# ab-berry-rev2.net
KiCad netlist of a schematic drawn in EAGLE
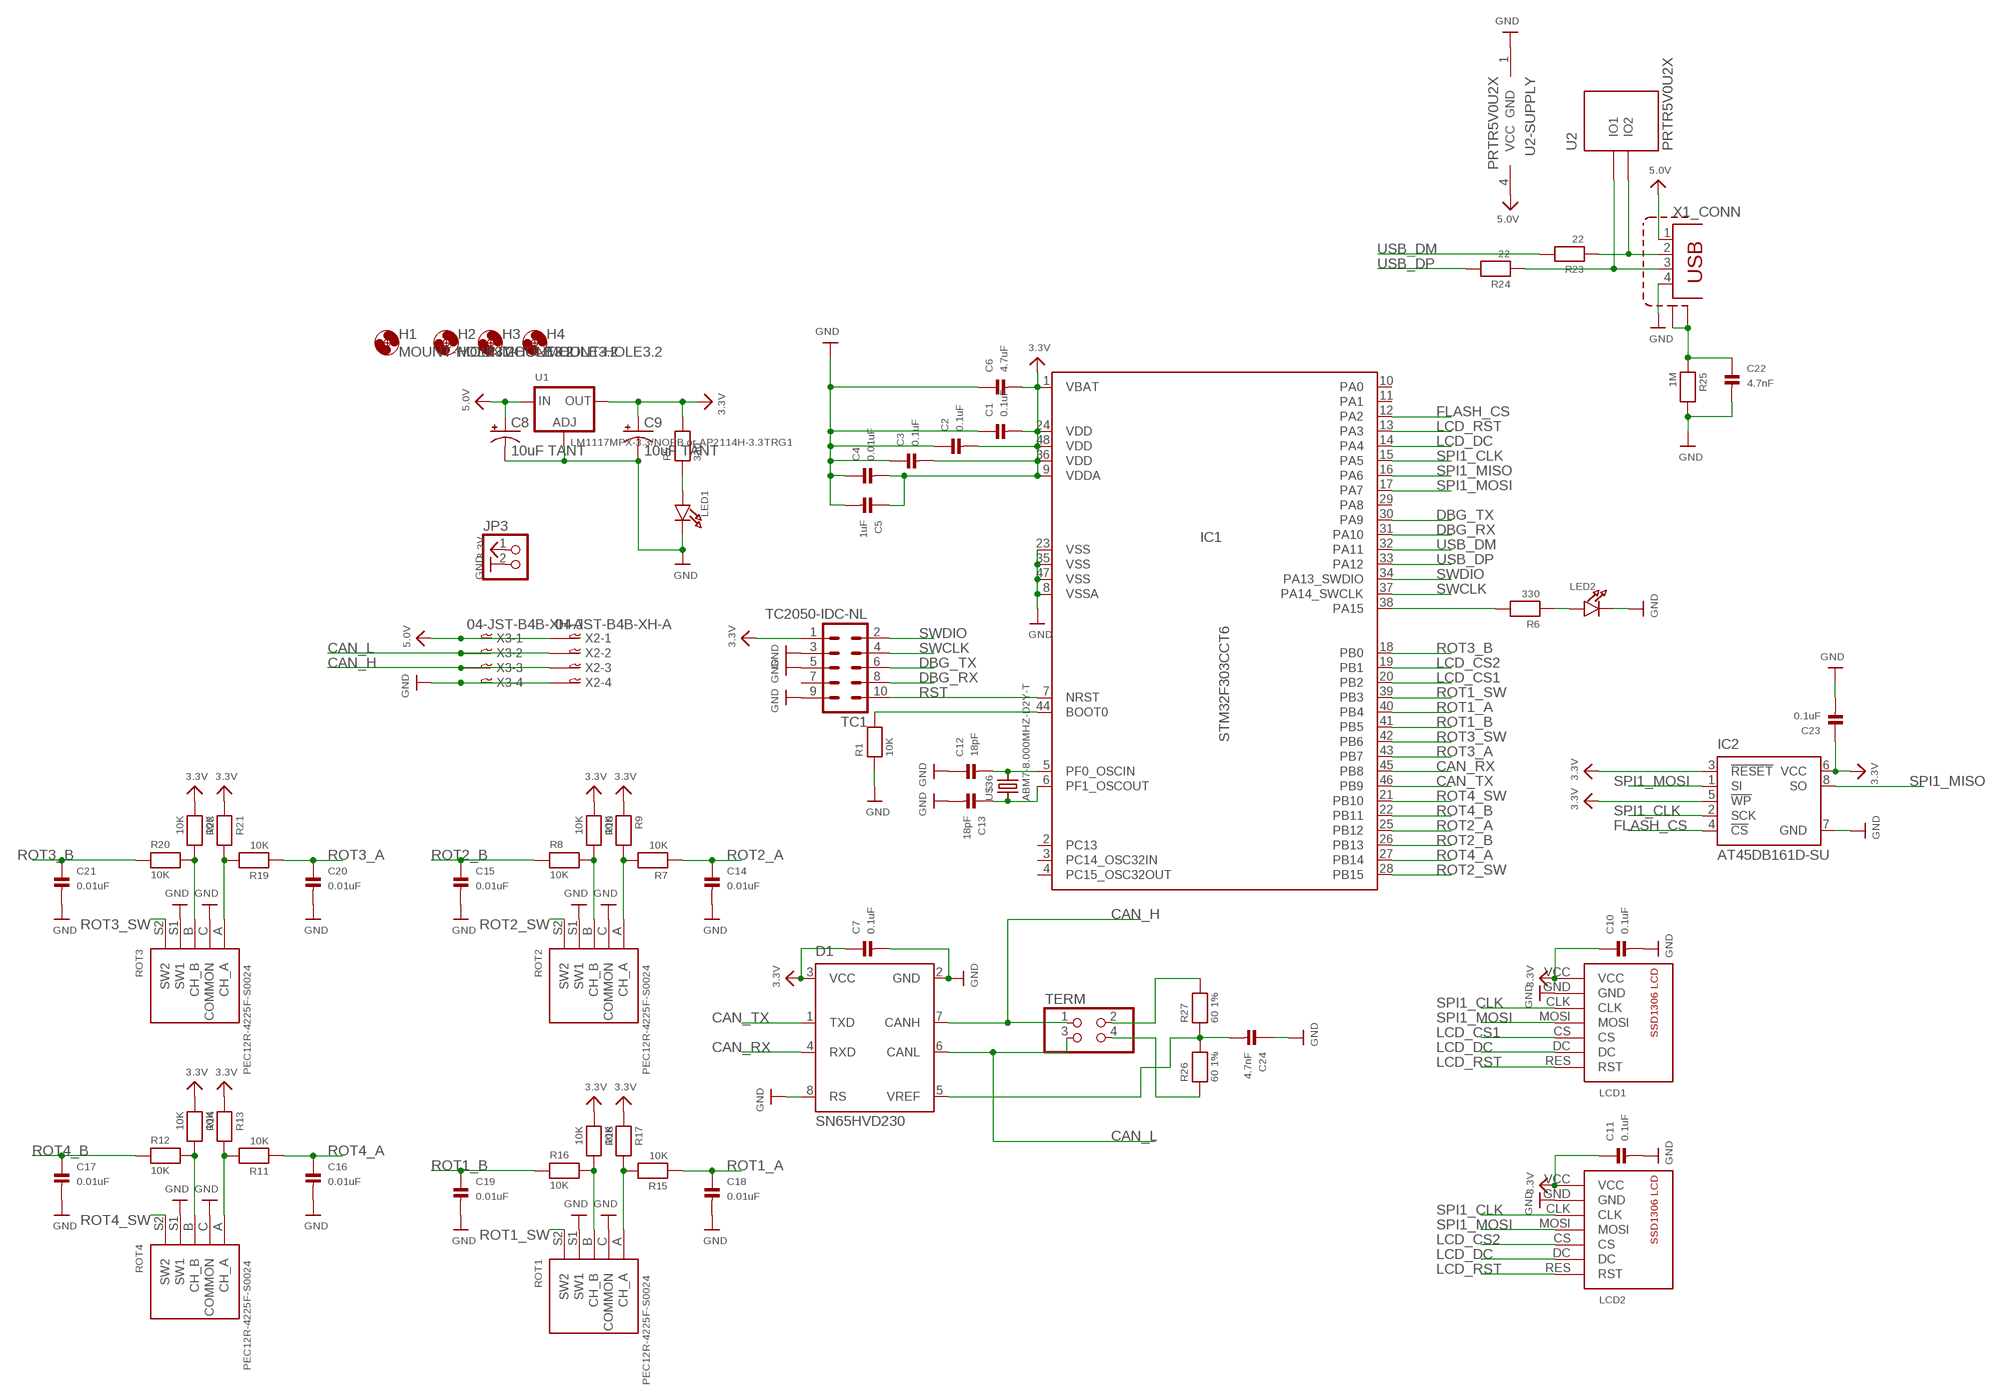
[diagram p0: schematic, sheet 1]

(export (version "E")
  (design (tool "Eeschema 10.0.6"))
  (components
    (comp (ref "C1")
      (value "0.1uF")
      (footprint "eagle-import:0603")
      (libsource (lib "eagle-import") (part "CAP_CERAMIC0603"))
    )
    (comp (ref "C2")
      (value "0.1uF")
      (footprint "eagle-import:0603")
      (libsource (lib "eagle-import") (part "CAP_CERAMIC0603"))
    )
    (comp (ref "C3")
      (value "0.1uF")
      (footprint "eagle-import:0603")
      (libsource (lib "eagle-import") (part "CAP_CERAMIC0603"))
    )
    (comp (ref "C4")
      (value "0.01uF")
      (footprint "eagle-import:0603")
      (libsource (lib "eagle-import") (part "CAP_CERAMIC0603"))
    )
    (comp (ref "C5")
      (value "1uF")
      (footprint "eagle-import:0603")
      (libsource (lib "eagle-import") (part "CAP_CERAMIC0603"))
    )
    (comp (ref "C6")
      (value "4.7uF")
      (footprint "eagle-import:0603")
      (libsource (lib "eagle-import") (part "CAP_CERAMIC0603"))
    )
    (comp (ref "C7")
      (value "0.1uF")
      (footprint "eagle-import:0603")
      (libsource (lib "eagle-import") (part "CAP_CERAMIC0603"))
    )
    (comp (ref "C8")
      (value "10uF TANT")
      (footprint "eagle-import:0603-POL")
      (libsource (lib "eagle-import") (part "10UF-6.3V-20%(0603)(TANT){dblquote}"))
    )
    (comp (ref "C9")
      (value "10uF TANT")
      (footprint "eagle-import:0603-POL")
      (libsource (lib "eagle-import") (part "10UF-6.3V-20%(0603)(TANT){dblquote}"))
    )
    (comp (ref "C10")
      (value "0.1uF")
      (footprint "eagle-import:0603")
      (libsource (lib "eagle-import") (part "CAP_CERAMIC0603"))
    )
    (comp (ref "C11")
      (value "0.1uF")
      (footprint "eagle-import:0603")
      (libsource (lib "eagle-import") (part "CAP_CERAMIC0603"))
    )
    (comp (ref "C12")
      (value "18pF")
      (footprint "eagle-import:0603")
      (libsource (lib "eagle-import") (part "CAP_CERAMIC0603"))
    )
    (comp (ref "C13")
      (value "18pF")
      (footprint "eagle-import:0603")
      (libsource (lib "eagle-import") (part "CAP_CERAMIC0603"))
    )
    (comp (ref "C14")
      (value "0.01uF")
      (footprint "eagle-import:0603")
      (libsource (lib "eagle-import") (part "CAP_CERAMIC0603"))
    )
    (comp (ref "C15")
      (value "0.01uF")
      (footprint "eagle-import:0603")
      (libsource (lib "eagle-import") (part "CAP_CERAMIC0603"))
    )
    (comp (ref "C16")
      (value "0.01uF")
      (footprint "eagle-import:0603")
      (libsource (lib "eagle-import") (part "CAP_CERAMIC0603"))
    )
    (comp (ref "C17")
      (value "0.01uF")
      (footprint "eagle-import:0603")
      (libsource (lib "eagle-import") (part "CAP_CERAMIC0603"))
    )
    (comp (ref "C18")
      (value "0.01uF")
      (footprint "eagle-import:0603")
      (libsource (lib "eagle-import") (part "CAP_CERAMIC0603"))
    )
    (comp (ref "C19")
      (value "0.01uF")
      (footprint "eagle-import:0603")
      (libsource (lib "eagle-import") (part "CAP_CERAMIC0603"))
    )
    (comp (ref "C20")
      (value "0.01uF")
      (footprint "eagle-import:0603")
      (libsource (lib "eagle-import") (part "CAP_CERAMIC0603"))
    )
    (comp (ref "C21")
      (value "0.01uF")
      (footprint "eagle-import:0603")
      (libsource (lib "eagle-import") (part "CAP_CERAMIC0603"))
    )
    (comp (ref "C22")
      (value "4.7nF")
      (footprint "eagle-import:0603")
      (libsource (lib "eagle-import") (part "CAP_CERAMIC0603"))
    )
    (comp (ref "C23")
      (value "0.1uF")
      (footprint "eagle-import:0603")
      (libsource (lib "eagle-import") (part "CAP_CERAMIC0603"))
    )
    (comp (ref "C24")
      (value "4.7nF")
      (footprint "eagle-import:0603")
      (libsource (lib "eagle-import") (part "CAP_CERAMIC0603"))
    )
    (comp (ref "D1")
      (value "SN65HVD230")
      (footprint "eagle-import:SO8")
      (libsource (lib "eagle-import") (part "SN65HVD230"))
    )
    (comp (ref "H1")
      (value "MOUNT-HOLE3.2")
      (footprint "eagle-import:3,2")
      (libsource (lib "eagle-import") (part "MOUNT-HOLE3.2"))
    )
    (comp (ref "H2")
      (value "MOUNT-HOLE3.2")
      (footprint "eagle-import:3,2")
      (libsource (lib "eagle-import") (part "MOUNT-HOLE3.2"))
    )
    (comp (ref "H3")
      (value "MOUNT-HOLE3.2")
      (footprint "eagle-import:3,2")
      (libsource (lib "eagle-import") (part "MOUNT-HOLE3.2"))
    )
    (comp (ref "H4")
      (value "MOUNT-HOLE3.2")
      (footprint "eagle-import:3,2")
      (libsource (lib "eagle-import") (part "MOUNT-HOLE3.2"))
    )
    (comp (ref "IC1")
      (value "STM32F303CCT6")
      (footprint "eagle-import:TQFP48")
      (libsource (lib "eagle-import") (part "STM32F302_F303_B_C_LQFP48"))
    )
    (comp (ref "IC2")
      (value "AT45DB161D-SU")
      (footprint "eagle-import:8S2")
      (fields (field (name "MF") "ATMEL"))
      (libsource (lib "eagle-import") (part "AT45DB161D-SU"))
    )
    (comp (ref "JP3")
      (value "PINHD-1X2")
      (footprint "eagle-import:1X02")
      (libsource (lib "eagle-import") (part "PINHD-1X2"))
    )
    (comp (ref "LCD1")
      (value "SSD1306-7PINWITHOUT-HOLES")
      (footprint "eagle-import:SSD1306-7PIN-NO-HOLES")
      (libsource (lib "eagle-import") (part "SSD1306-7PINWITHOUT-HOLES"))
    )
    (comp (ref "LCD2")
      (value "SSD1306-7PINWITHOUT-HOLES")
      (footprint "eagle-import:SSD1306-7PIN-NO-HOLES")
      (libsource (lib "eagle-import") (part "SSD1306-7PINWITHOUT-HOLES"))
    )
    (comp (ref "LED1")
      (value "LED0603")
      (footprint "eagle-import:CHIPLED_0603")
      (libsource (lib "eagle-import") (part "LED0603"))
    )
    (comp (ref "LED2")
      (value "LED0603")
      (footprint "eagle-import:CHIPLED_0603")
      (libsource (lib "eagle-import") (part "LED0603"))
    )
    (comp (ref "R1")
      (value "10K")
      (footprint "eagle-import:0603")
      (libsource (lib "eagle-import") (part "RESISTOR0603"))
    )
    (comp (ref "R5")
      (value "330")
      (footprint "eagle-import:0603")
      (libsource (lib "eagle-import") (part "RESISTOR0603"))
    )
    (comp (ref "R6")
      (value "330")
      (footprint "eagle-import:0603")
      (libsource (lib "eagle-import") (part "RESISTOR0603"))
    )
    (comp (ref "R7")
      (value "10K")
      (footprint "eagle-import:0603")
      (libsource (lib "eagle-import") (part "RESISTOR0603"))
    )
    (comp (ref "R8")
      (value "10K")
      (footprint "eagle-import:0603")
      (libsource (lib "eagle-import") (part "RESISTOR0603"))
    )
    (comp (ref "R9")
      (value "10K")
      (footprint "eagle-import:0603")
      (libsource (lib "eagle-import") (part "RESISTOR0603"))
    )
    (comp (ref "R10")
      (value "10K")
      (footprint "eagle-import:0603")
      (libsource (lib "eagle-import") (part "RESISTOR0603"))
    )
    (comp (ref "R11")
      (value "10K")
      (footprint "eagle-import:0603")
      (libsource (lib "eagle-import") (part "RESISTOR0603"))
    )
    (comp (ref "R12")
      (value "10K")
      (footprint "eagle-import:0603")
      (libsource (lib "eagle-import") (part "RESISTOR0603"))
    )
    (comp (ref "R13")
      (value "10K")
      (footprint "eagle-import:0603")
      (libsource (lib "eagle-import") (part "RESISTOR0603"))
    )
    (comp (ref "R14")
      (value "10K")
      (footprint "eagle-import:0603")
      (libsource (lib "eagle-import") (part "RESISTOR0603"))
    )
    (comp (ref "R15")
      (value "10K")
      (footprint "eagle-import:0603")
      (libsource (lib "eagle-import") (part "RESISTOR0603"))
    )
    (comp (ref "R16")
      (value "10K")
      (footprint "eagle-import:0603")
      (libsource (lib "eagle-import") (part "RESISTOR0603"))
    )
    (comp (ref "R17")
      (value "10K")
      (footprint "eagle-import:0603")
      (libsource (lib "eagle-import") (part "RESISTOR0603"))
    )
    (comp (ref "R18")
      (value "10K")
      (footprint "eagle-import:0603")
      (libsource (lib "eagle-import") (part "RESISTOR0603"))
    )
    (comp (ref "R19")
      (value "10K")
      (footprint "eagle-import:0603")
      (libsource (lib "eagle-import") (part "RESISTOR0603"))
    )
    (comp (ref "R20")
      (value "10K")
      (footprint "eagle-import:0603")
      (libsource (lib "eagle-import") (part "RESISTOR0603"))
    )
    (comp (ref "R21")
      (value "10K")
      (footprint "eagle-import:0603")
      (libsource (lib "eagle-import") (part "RESISTOR0603"))
    )
    (comp (ref "R22")
      (value "10K")
      (footprint "eagle-import:0603")
      (libsource (lib "eagle-import") (part "RESISTOR0603"))
    )
    (comp (ref "R23")
      (value "22")
      (footprint "eagle-import:0603")
      (libsource (lib "eagle-import") (part "RESISTOR0603"))
    )
    (comp (ref "R24")
      (value "22")
      (footprint "eagle-import:0603")
      (libsource (lib "eagle-import") (part "RESISTOR0603"))
    )
    (comp (ref "R25")
      (value "1M")
      (footprint "eagle-import:0603")
      (libsource (lib "eagle-import") (part "RESISTOR0603"))
    )
    (comp (ref "R26")
      (value "60 1%")
      (footprint "eagle-import:0603")
      (libsource (lib "eagle-import") (part "RESISTOR0603"))
    )
    (comp (ref "R27")
      (value "60 1%")
      (footprint "eagle-import:0603")
      (libsource (lib "eagle-import") (part "RESISTOR0603"))
    )
    (comp (ref "ROT1")
      (value "PEC12R-4225F-S0024")
      (footprint "eagle-import:PEC111-4XXXK-SXXXX")
      (libsource (lib "eagle-import") (part "PEC11-4215K-S0024"))
    )
    (comp (ref "ROT2")
      (value "PEC12R-4225F-S0024")
      (footprint "eagle-import:PEC111-4XXXK-SXXXX")
      (libsource (lib "eagle-import") (part "PEC11-4215K-S0024"))
    )
    (comp (ref "ROT3")
      (value "PEC12R-4225F-S0024")
      (footprint "eagle-import:PEC111-4XXXK-SXXXX")
      (libsource (lib "eagle-import") (part "PEC11-4215K-S0024"))
    )
    (comp (ref "ROT4")
      (value "PEC12R-4225F-S0024")
      (footprint "eagle-import:PEC111-4XXXK-SXXXX")
      (libsource (lib "eagle-import") (part "PEC11-4215K-S0024"))
    )
    (comp (ref "TC1")
      (value "TC2050-IDC-NL")
      (footprint "eagle-import:TC2050-IDC-NL")
      (libsource (lib "eagle-import") (part "TC2050-IDC-NL"))
    )
    (comp (ref "TERM")
      (value "PINHD-2X2")
      (footprint "eagle-import:2X02")
      (libsource (lib "eagle-import") (part "PINHD-2X2"))
    )
    (comp (ref "U$36")
      (value "ABM7-8.000MHZ-D2Y-T")
      (footprint "eagle-import:ABM7-8.000MHZ-D2Y-T")
      (libsource (lib "eagle-import") (part "ABM7-8.000MHZ-D2Y-T"))
    )
    (comp (ref "U1")
      (value "LM1117MPX-3.3/NOPB or AP2114H-3.3TRG1")
      (footprint "eagle-import:SOT223-R")
      (libsource (lib "eagle-import") (part "LM1117SOT223-REFLOW"))
    )
    (comp (ref "U2")
      (value "PRTR5V0U2X")
      (footprint "eagle-import:SOT-143B")
      (fields
        (field (name "MANUFACTURER") "NXP Semiconductors")
        (field (name "PART_NUMBER") "PRTR5V0U2X,215")
      )
      (libsource (lib "eagle-import") (part "PRTR5V0U2X?"))
    )
    (comp (ref "X1")
      (value "TE-292304-1")
      (footprint "eagle-import:TE-292304-1")
      (libsource (lib "eagle-import") (part "TE-292304-1"))
    )
    (comp (ref "X2")
      (value "04-JST-B4B-XH-A")
      (footprint "eagle-import:B4B-XH")
      (libsource (lib "eagle-import") (part "04-JST-B4B-XH-A"))
    )
    (comp (ref "X3")
      (value "04-JST-B4B-XH-A")
      (footprint "eagle-import:B4B-XH")
      (libsource (lib "eagle-import") (part "04-JST-B4B-XH-A"))
    )
  )
  (nets
    (net (code "1") (name "/CAN_H") (class "Default")
      (node (ref "D1") (pin "7") (pinfunction "CANH_7") (pintype "bidirectional"))
      (node (ref "TERM") (pin "1") (pinfunction "1_1") (pintype "passive"))
      (node (ref "X2") (pin "P$3") (pinfunction "1_P$3") (pintype "passive"))
      (node (ref "X3") (pin "P$3") (pinfunction "1_P$3") (pintype "passive"))
    )
    (net (code "2") (name "/CAN_L") (class "Default")
      (node (ref "D1") (pin "6") (pinfunction "CANL_6") (pintype "bidirectional"))
      (node (ref "TERM") (pin "3") (pinfunction "3_3") (pintype "passive"))
      (node (ref "X2") (pin "P$2") (pinfunction "1_P$2") (pintype "passive"))
      (node (ref "X3") (pin "P$2") (pinfunction "1_P$2") (pintype "passive"))
    )
    (net (code "3") (name "/CAN_RX") (class "Default")
      (node (ref "D1") (pin "4") (pinfunction "RXD_4") (pintype "output"))
      (node (ref "IC1") (pin "45") (pinfunction "PB8_45") (pintype "bidirectional"))
    )
    (net (code "4") (name "/CAN_TX") (class "Default")
      (node (ref "D1") (pin "1") (pinfunction "TXD_1") (pintype "input"))
      (node (ref "IC1") (pin "46") (pinfunction "PB9_46") (pintype "bidirectional"))
    )
    (net (code "5") (name "/DBG_RX") (class "Default")
      (node (ref "IC1") (pin "31") (pinfunction "PA10_31") (pintype "bidirectional"))
      (node (ref "TC1") (pin "8") (pinfunction "8_8") (pintype "passive"))
    )
    (net (code "6") (name "/DBG_TX") (class "Default")
      (node (ref "IC1") (pin "30") (pinfunction "PA9_30") (pintype "bidirectional"))
      (node (ref "TC1") (pin "6") (pinfunction "6_6") (pintype "passive"))
    )
    (net (code "7") (name "/FLASH_CS") (class "Default")
      (node (ref "IC1") (pin "12") (pinfunction "PA2_12") (pintype "bidirectional"))
      (node (ref "IC2") (pin "4") (pinfunction "~{CS}_4") (pintype "input"))
    )
    (net (code "8") (name "/LCD_CS1") (class "Default")
      (node (ref "IC1") (pin "20") (pinfunction "PB2_20") (pintype "bidirectional"))
      (node (ref "LCD1") (pin "CS") (pinfunction "CS_CS") (pintype "bidirectional"))
    )
    (net (code "9") (name "/LCD_CS2") (class "Default")
      (node (ref "IC1") (pin "19") (pinfunction "PB1_19") (pintype "bidirectional"))
      (node (ref "LCD2") (pin "CS") (pinfunction "CS_CS") (pintype "bidirectional"))
    )
    (net (code "10") (name "/LCD_DC") (class "Default")
      (node (ref "IC1") (pin "14") (pinfunction "PA4_14") (pintype "bidirectional"))
      (node (ref "LCD1") (pin "DC") (pinfunction "DC_DC") (pintype "bidirectional"))
      (node (ref "LCD2") (pin "DC") (pinfunction "DC_DC") (pintype "bidirectional"))
    )
    (net (code "11") (name "/LCD_RST") (class "Default")
      (node (ref "IC1") (pin "13") (pinfunction "PA3_13") (pintype "bidirectional"))
      (node (ref "LCD1") (pin "RES") (pinfunction "RST_RES") (pintype "bidirectional"))
      (node (ref "LCD2") (pin "RES") (pinfunction "RST_RES") (pintype "bidirectional"))
    )
    (net (code "12") (name "/ROT1_A") (class "Default")
      (node (ref "C18") (pin "1") (pinfunction "P$1_1") (pintype "passive"))
      (node (ref "IC1") (pin "40") (pinfunction "PB4_40") (pintype "input"))
      (node (ref "R15") (pin "1") (pinfunction "1_1") (pintype "passive"))
    )
    (net (code "13") (name "/ROT1_B") (class "Default")
      (node (ref "C19") (pin "1") (pinfunction "P$1_1") (pintype "passive"))
      (node (ref "IC1") (pin "41") (pinfunction "PB5_41") (pintype "bidirectional"))
      (node (ref "R16") (pin "1") (pinfunction "1_1") (pintype "passive"))
    )
    (net (code "14") (name "/ROT1_SW") (class "Default")
      (node (ref "IC1") (pin "39") (pinfunction "PB3_39") (pintype "output"))
      (node (ref "ROT1") (pin "S2") (pinfunction "SW2_S2") (pintype "bidirectional"))
    )
    (net (code "15") (name "/ROT2_A") (class "Default")
      (node (ref "C14") (pin "1") (pinfunction "P$1_1") (pintype "passive"))
      (node (ref "IC1") (pin "25") (pinfunction "PB12_25") (pintype "bidirectional"))
      (node (ref "R7") (pin "1") (pinfunction "1_1") (pintype "passive"))
    )
    (net (code "16") (name "/ROT2_B") (class "Default")
      (node (ref "C15") (pin "1") (pinfunction "P$1_1") (pintype "passive"))
      (node (ref "IC1") (pin "26") (pinfunction "PB13_26") (pintype "bidirectional"))
      (node (ref "R8") (pin "1") (pinfunction "1_1") (pintype "passive"))
    )
    (net (code "17") (name "/ROT2_SW") (class "Default")
      (node (ref "IC1") (pin "28") (pinfunction "PB15_28") (pintype "bidirectional"))
      (node (ref "ROT2") (pin "S2") (pinfunction "SW2_S2") (pintype "bidirectional"))
    )
    (net (code "18") (name "/ROT3_A") (class "Default")
      (node (ref "C20") (pin "1") (pinfunction "P$1_1") (pintype "passive"))
      (node (ref "IC1") (pin "43") (pinfunction "PB7_43") (pintype "bidirectional"))
      (node (ref "R19") (pin "1") (pinfunction "1_1") (pintype "passive"))
    )
    (net (code "19") (name "/ROT3_B") (class "Default")
      (node (ref "C21") (pin "1") (pinfunction "P$1_1") (pintype "passive"))
      (node (ref "IC1") (pin "18") (pinfunction "PB0_18") (pintype "bidirectional"))
      (node (ref "R20") (pin "1") (pinfunction "1_1") (pintype "passive"))
    )
    (net (code "20") (name "/ROT3_SW") (class "Default")
      (node (ref "IC1") (pin "42") (pinfunction "PB6_42") (pintype "bidirectional"))
      (node (ref "ROT3") (pin "S2") (pinfunction "SW2_S2") (pintype "bidirectional"))
    )
    (net (code "21") (name "/ROT4_A") (class "Default")
      (node (ref "C16") (pin "1") (pinfunction "P$1_1") (pintype "passive"))
      (node (ref "IC1") (pin "27") (pinfunction "PB14_27") (pintype "bidirectional"))
      (node (ref "R11") (pin "1") (pinfunction "1_1") (pintype "passive"))
    )
    (net (code "22") (name "/ROT4_B") (class "Default")
      (node (ref "C17") (pin "1") (pinfunction "P$1_1") (pintype "passive"))
      (node (ref "IC1") (pin "22") (pinfunction "PB11_22") (pintype "bidirectional"))
      (node (ref "R12") (pin "1") (pinfunction "1_1") (pintype "passive"))
    )
    (net (code "23") (name "/ROT4_SW") (class "Default")
      (node (ref "IC1") (pin "21") (pinfunction "PB10_21") (pintype "bidirectional"))
      (node (ref "ROT4") (pin "S2") (pinfunction "SW2_S2") (pintype "bidirectional"))
    )
    (net (code "24") (name "/RST") (class "Default")
      (node (ref "IC1") (pin "7") (pinfunction "NRST_7") (pintype "input"))
      (node (ref "TC1") (pin "10") (pinfunction "10_10") (pintype "passive"))
    )
    (net (code "25") (name "/SPI1_CLK") (class "Default")
      (node (ref "IC1") (pin "15") (pinfunction "PA5_15") (pintype "bidirectional"))
      (node (ref "IC2") (pin "2") (pinfunction "SCK_2") (pintype "input"))
      (node (ref "LCD1") (pin "CLK") (pinfunction "CLK_CLK") (pintype "bidirectional"))
      (node (ref "LCD2") (pin "CLK") (pinfunction "CLK_CLK") (pintype "bidirectional"))
    )
    (net (code "26") (name "/SPI1_MISO") (class "Default")
      (node (ref "IC1") (pin "16") (pinfunction "PA6_16") (pintype "bidirectional"))
      (node (ref "IC2") (pin "8") (pinfunction "SO_8") (pintype "output"))
    )
    (net (code "27") (name "/SPI1_MOSI") (class "Default")
      (node (ref "IC1") (pin "17") (pinfunction "PA7_17") (pintype "bidirectional"))
      (node (ref "IC2") (pin "1") (pinfunction "SI_1") (pintype "input"))
      (node (ref "LCD1") (pin "MOSI") (pinfunction "MOSI_MOSI") (pintype "bidirectional"))
      (node (ref "LCD2") (pin "MOSI") (pinfunction "MOSI_MOSI") (pintype "bidirectional"))
    )
    (net (code "28") (name "/SWCLK") (class "Default")
      (node (ref "IC1") (pin "37") (pinfunction "PA14_SWCLK_37") (pintype "input"))
      (node (ref "TC1") (pin "4") (pinfunction "4_4") (pintype "passive"))
    )
    (net (code "29") (name "/SWDIO") (class "Default")
      (node (ref "IC1") (pin "34") (pinfunction "PA13_SWDIO_34") (pintype "input"))
      (node (ref "TC1") (pin "2") (pinfunction "2_2") (pintype "passive"))
    )
    (net (code "30") (name "/USB_DM") (class "Default")
      (node (ref "IC1") (pin "32") (pinfunction "PA11_32") (pintype "bidirectional"))
      (node (ref "R23") (pin "2") (pinfunction "2_2") (pintype "passive"))
    )
    (net (code "31") (name "/USB_DP") (class "Default")
      (node (ref "IC1") (pin "33") (pinfunction "PA12_33") (pintype "bidirectional"))
      (node (ref "R24") (pin "2") (pinfunction "2_2") (pintype "passive"))
    )
    (net (code "32") (name "3.3V") (class "Default")
      (node (ref "C1") (pin "2") (pinfunction "P$2_2") (pintype "passive"))
      (node (ref "C10") (pin "1") (pinfunction "P$1_1") (pintype "passive"))
      (node (ref "C11") (pin "1") (pinfunction "P$1_1") (pintype "passive"))
      (node (ref "C2") (pin "2") (pinfunction "P$2_2") (pintype "passive"))
      (node (ref "C23") (pin "1") (pinfunction "P$1_1") (pintype "passive"))
      (node (ref "C3") (pin "2") (pinfunction "P$2_2") (pintype "passive"))
      (node (ref "C4") (pin "2") (pinfunction "P$2_2") (pintype "passive"))
      (node (ref "C5") (pin "1") (pinfunction "P$1_1") (pintype "passive"))
      (node (ref "C6") (pin "2") (pinfunction "P$2_2") (pintype "passive"))
      (node (ref "C7") (pin "1") (pinfunction "P$1_1") (pintype "passive"))
      (node (ref "C9") (pin "A") (pinfunction "+_A") (pintype "passive"))
      (node (ref "D1") (pin "3") (pinfunction "VCC_3") (pintype "power_in"))
      (node (ref "IC1") (pin "1") (pinfunction "VBAT_1") (pintype "passive"))
      (node (ref "IC1") (pin "24") (pinfunction "VDD_24") (pintype "power_in"))
      (node (ref "IC1") (pin "36") (pinfunction "VDD_36") (pintype "power_in"))
      (node (ref "IC1") (pin "48") (pinfunction "VDD_48") (pintype "power_in"))
      (node (ref "IC1") (pin "9") (pinfunction "VDDA_9") (pintype "power_in"))
      (node (ref "IC2") (pin "3") (pinfunction "~{RESET}_3") (pintype "input"))
      (node (ref "IC2") (pin "5") (pinfunction "~{WP}_5") (pintype "input"))
      (node (ref "IC2") (pin "6") (pinfunction "VCC_6") (pintype "power_in"))
      (node (ref "JP3") (pin "1") (pinfunction "1_1") (pintype "passive"))
      (node (ref "LCD1") (pin "VCC") (pinfunction "VCC_VCC") (pintype "bidirectional"))
      (node (ref "LCD2") (pin "VCC") (pinfunction "VCC_VCC") (pintype "bidirectional"))
      (node (ref "R10") (pin "1") (pinfunction "1_1") (pintype "passive"))
      (node (ref "R13") (pin "1") (pinfunction "1_1") (pintype "passive"))
      (node (ref "R14") (pin "1") (pinfunction "1_1") (pintype "passive"))
      (node (ref "R17") (pin "1") (pinfunction "1_1") (pintype "passive"))
      (node (ref "R18") (pin "1") (pinfunction "1_1") (pintype "passive"))
      (node (ref "R21") (pin "1") (pinfunction "1_1") (pintype "passive"))
      (node (ref "R22") (pin "1") (pinfunction "1_1") (pintype "passive"))
      (node (ref "R5") (pin "2") (pinfunction "2_2") (pintype "passive"))
      (node (ref "R9") (pin "1") (pinfunction "1_1") (pintype "passive"))
      (node (ref "TC1") (pin "1") (pinfunction "1_1") (pintype "passive"))
      (node (ref "U1") (pin "2") (pinfunction "OUT_2") (pintype "passive"))
    )
    (net (code "33") (name "5.0V") (class "Default")
      (node (ref "C8") (pin "A") (pinfunction "+_A") (pintype "passive"))
      (node (ref "U1") (pin "3") (pinfunction "IN_3") (pintype "input"))
      (node (ref "U2") (pin "4") (pinfunction "VCC_4") (pintype "bidirectional"))
      (node (ref "X1") (pin "1") (pinfunction "1_1") (pintype "bidirectional"))
      (node (ref "X2") (pin "P$1") (pinfunction "1_P$1") (pintype "passive"))
      (node (ref "X3") (pin "P$1") (pinfunction "1_P$1") (pintype "passive"))
    )
    (net (code "34") (name "GND") (class "Default")
      (node (ref "C1") (pin "1") (pinfunction "P$1_1") (pintype "passive"))
      (node (ref "C10") (pin "2") (pinfunction "P$2_2") (pintype "passive"))
      (node (ref "C11") (pin "2") (pinfunction "P$2_2") (pintype "passive"))
      (node (ref "C12") (pin "1") (pinfunction "P$1_1") (pintype "passive"))
      (node (ref "C13") (pin "2") (pinfunction "P$2_2") (pintype "passive"))
      (node (ref "C14") (pin "2") (pinfunction "P$2_2") (pintype "passive"))
      (node (ref "C15") (pin "2") (pinfunction "P$2_2") (pintype "passive"))
      (node (ref "C16") (pin "2") (pinfunction "P$2_2") (pintype "passive"))
      (node (ref "C17") (pin "2") (pinfunction "P$2_2") (pintype "passive"))
      (node (ref "C18") (pin "2") (pinfunction "P$2_2") (pintype "passive"))
      (node (ref "C19") (pin "2") (pinfunction "P$2_2") (pintype "passive"))
      (node (ref "C2") (pin "1") (pinfunction "P$1_1") (pintype "passive"))
      (node (ref "C20") (pin "2") (pinfunction "P$2_2") (pintype "passive"))
      (node (ref "C21") (pin "2") (pinfunction "P$2_2") (pintype "passive"))
      (node (ref "C22") (pin "2") (pinfunction "P$2_2") (pintype "passive"))
      (node (ref "C23") (pin "2") (pinfunction "P$2_2") (pintype "passive"))
      (node (ref "C24") (pin "1") (pinfunction "P$1_1") (pintype "passive"))
      (node (ref "C3") (pin "1") (pinfunction "P$1_1") (pintype "passive"))
      (node (ref "C4") (pin "1") (pinfunction "P$1_1") (pintype "passive"))
      (node (ref "C5") (pin "2") (pinfunction "P$2_2") (pintype "passive"))
      (node (ref "C6") (pin "1") (pinfunction "P$1_1") (pintype "passive"))
      (node (ref "C7") (pin "2") (pinfunction "P$2_2") (pintype "passive"))
      (node (ref "C8") (pin "K") (pinfunction "-_K") (pintype "passive"))
      (node (ref "C9") (pin "K") (pinfunction "-_K") (pintype "passive"))
      (node (ref "D1") (pin "2") (pinfunction "GND_2") (pintype "power_in"))
      (node (ref "D1") (pin "8") (pinfunction "RS_8") (pintype "input"))
      (node (ref "IC1") (pin "23") (pinfunction "VSS_23") (pintype "power_in"))
      (node (ref "IC1") (pin "35") (pinfunction "VSS_35") (pintype "power_in"))
      (node (ref "IC1") (pin "47") (pinfunction "VSS_47") (pintype "power_in"))
      (node (ref "IC1") (pin "8") (pinfunction "VSSA_8") (pintype "power_in"))
      (node (ref "IC2") (pin "7") (pinfunction "GND_7") (pintype "power_in"))
      (node (ref "JP3") (pin "2") (pinfunction "2_2") (pintype "passive"))
      (node (ref "LCD1") (pin "GND") (pinfunction "GND_GND") (pintype "bidirectional"))
      (node (ref "LCD2") (pin "GND") (pinfunction "GND_GND") (pintype "bidirectional"))
      (node (ref "LED1") (pin "C") (pinfunction "C_C") (pintype "passive"))
      (node (ref "LED2") (pin "C") (pinfunction "C_C") (pintype "passive"))
      (node (ref "R1") (pin "1") (pinfunction "1_1") (pintype "passive"))
      (node (ref "R25") (pin "2") (pinfunction "2_2") (pintype "passive"))
      (node (ref "ROT1") (pin "C") (pinfunction "COMMON_C") (pintype "input"))
      (node (ref "ROT1") (pin "S1") (pinfunction "SW1_S1") (pintype "bidirectional"))
      (node (ref "ROT2") (pin "C") (pinfunction "COMMON_C") (pintype "input"))
      (node (ref "ROT2") (pin "S1") (pinfunction "SW1_S1") (pintype "bidirectional"))
      (node (ref "ROT3") (pin "C") (pinfunction "COMMON_C") (pintype "input"))
      (node (ref "ROT3") (pin "S1") (pinfunction "SW1_S1") (pintype "bidirectional"))
      (node (ref "ROT4") (pin "C") (pinfunction "COMMON_C") (pintype "input"))
      (node (ref "ROT4") (pin "S1") (pinfunction "SW1_S1") (pintype "bidirectional"))
      (node (ref "TC1") (pin "3") (pinfunction "3_3") (pintype "passive"))
      (node (ref "TC1") (pin "5") (pinfunction "5_5") (pintype "passive"))
      (node (ref "TC1") (pin "9") (pinfunction "9_9") (pintype "passive"))
      (node (ref "U1") (pin "1") (pinfunction "ADJ_1") (pintype "input"))
      (node (ref "U2") (pin "1") (pinfunction "GND_1") (pintype "bidirectional"))
      (node (ref "X1") (pin "4") (pinfunction "4_4") (pintype "bidirectional"))
      (node (ref "X2") (pin "P$4") (pinfunction "1_P$4") (pintype "passive"))
      (node (ref "X3") (pin "P$4") (pinfunction "1_P$4") (pintype "passive"))
    )
    (net (code "35") (name "Net-(C12-P$2)") (class "Default")
      (node (ref "C12") (pin "2") (pinfunction "P$2_2") (pintype "passive"))
      (node (ref "IC1") (pin "5") (pinfunction "PF0_OSCIN_5") (pintype "bidirectional"))
      (node (ref "U$36") (pin "P$2") (pinfunction "2_P$2") (pintype "passive"))
    )
    (net (code "36") (name "Net-(C13-P$1)") (class "Default")
      (node (ref "C13") (pin "1") (pinfunction "P$1_1") (pintype "passive"))
      (node (ref "IC1") (pin "6") (pinfunction "PF1_OSCOUT_6") (pintype "bidirectional"))
      (node (ref "U$36") (pin "P$1") (pinfunction "1_P$1") (pintype "passive"))
    )
    (net (code "37") (name "Net-(C22-P$1)") (class "Default")
      (node (ref "C22") (pin "1") (pinfunction "P$1_1") (pintype "passive"))
      (node (ref "R25") (pin "1") (pinfunction "1_1") (pintype "passive"))
      (node (ref "X1") (pin "P$1") (pinfunction "S1_P$1") (pintype "passive"))
      (node (ref "X1") (pin "P$2") (pinfunction "S2_P$2") (pintype "passive"))
    )
    (net (code "38") (name "Net-(C24-P$2)") (class "Default")
      (node (ref "C24") (pin "2") (pinfunction "P$2_2") (pintype "passive"))
      (node (ref "D1") (pin "5") (pinfunction "VREF_5") (pintype "output"))
      (node (ref "R26") (pin "2") (pinfunction "2_2") (pintype "passive"))
      (node (ref "R27") (pin "1") (pinfunction "1_1") (pintype "passive"))
    )
    (net (code "39") (name "Net-(IC1-BOOT0)") (class "Default")
      (node (ref "IC1") (pin "44") (pinfunction "BOOT0_44") (pintype "input"))
      (node (ref "R1") (pin "2") (pinfunction "2_2") (pintype "passive"))
    )
    (net (code "40") (name "Net-(IC1-PA15)") (class "Default")
      (node (ref "IC1") (pin "38") (pinfunction "PA15_38") (pintype "input"))
      (node (ref "R6") (pin "2") (pinfunction "2_2") (pintype "passive"))
    )
    (net (code "41") (name "Net-(LED1-PadA)") (class "Default")
      (node (ref "LED1") (pin "A") (pinfunction "A_A") (pintype "passive"))
      (node (ref "R5") (pin "1") (pinfunction "1_1") (pintype "passive"))
    )
    (net (code "42") (name "Net-(LED2-PadA)") (class "Default")
      (node (ref "LED2") (pin "A") (pinfunction "A_A") (pintype "passive"))
      (node (ref "R6") (pin "1") (pinfunction "1_1") (pintype "passive"))
    )
    (net (code "43") (name "Net-(R26-Pad1)") (class "Default")
      (node (ref "R26") (pin "1") (pinfunction "1_1") (pintype "passive"))
      (node (ref "TERM") (pin "4") (pinfunction "4_4") (pintype "passive"))
    )
    (net (code "44") (name "Net-(R27-Pad2)") (class "Default")
      (node (ref "R27") (pin "2") (pinfunction "2_2") (pintype "passive"))
      (node (ref "TERM") (pin "2") (pinfunction "2_2") (pintype "passive"))
    )
    (net (code "45") (name "Net-(ROT1-CH_A)") (class "Default")
      (node (ref "R15") (pin "2") (pinfunction "2_2") (pintype "passive"))
      (node (ref "R17") (pin "2") (pinfunction "2_2") (pintype "passive"))
      (node (ref "ROT1") (pin "A") (pinfunction "CH_A_A") (pintype "output"))
    )
    (net (code "46") (name "Net-(ROT1-CH_B)") (class "Default")
      (node (ref "R16") (pin "2") (pinfunction "2_2") (pintype "passive"))
      (node (ref "R18") (pin "2") (pinfunction "2_2") (pintype "passive"))
      (node (ref "ROT1") (pin "B") (pinfunction "CH_B_B") (pintype "output"))
    )
    (net (code "47") (name "Net-(ROT2-CH_A)") (class "Default")
      (node (ref "R7") (pin "2") (pinfunction "2_2") (pintype "passive"))
      (node (ref "R9") (pin "2") (pinfunction "2_2") (pintype "passive"))
      (node (ref "ROT2") (pin "A") (pinfunction "CH_A_A") (pintype "output"))
    )
    (net (code "48") (name "Net-(ROT2-CH_B)") (class "Default")
      (node (ref "R10") (pin "2") (pinfunction "2_2") (pintype "passive"))
      (node (ref "R8") (pin "2") (pinfunction "2_2") (pintype "passive"))
      (node (ref "ROT2") (pin "B") (pinfunction "CH_B_B") (pintype "output"))
    )
    (net (code "49") (name "Net-(ROT3-CH_A)") (class "Default")
      (node (ref "R19") (pin "2") (pinfunction "2_2") (pintype "passive"))
      (node (ref "R21") (pin "2") (pinfunction "2_2") (pintype "passive"))
      (node (ref "ROT3") (pin "A") (pinfunction "CH_A_A") (pintype "output"))
    )
    (net (code "50") (name "Net-(ROT3-CH_B)") (class "Default")
      (node (ref "R20") (pin "2") (pinfunction "2_2") (pintype "passive"))
      (node (ref "R22") (pin "2") (pinfunction "2_2") (pintype "passive"))
      (node (ref "ROT3") (pin "B") (pinfunction "CH_B_B") (pintype "output"))
    )
    (net (code "51") (name "Net-(ROT4-CH_A)") (class "Default")
      (node (ref "R11") (pin "2") (pinfunction "2_2") (pintype "passive"))
      (node (ref "R13") (pin "2") (pinfunction "2_2") (pintype "passive"))
      (node (ref "ROT4") (pin "A") (pinfunction "CH_A_A") (pintype "output"))
    )
    (net (code "52") (name "Net-(ROT4-CH_B)") (class "Default")
      (node (ref "R12") (pin "2") (pinfunction "2_2") (pintype "passive"))
      (node (ref "R14") (pin "2") (pinfunction "2_2") (pintype "passive"))
      (node (ref "ROT4") (pin "B") (pinfunction "CH_B_B") (pintype "output"))
    )
    (net (code "53") (name "Net-(U2B-IO1)") (class "Default")
      (node (ref "R24") (pin "1") (pinfunction "1_1") (pintype "passive"))
      (node (ref "U2") (pin "2") (pinfunction "IO1_2") (pintype "bidirectional"))
      (node (ref "X1") (pin "3") (pinfunction "3_3") (pintype "bidirectional"))
    )
    (net (code "54") (name "Net-(U2B-IO2)") (class "Default")
      (node (ref "R23") (pin "1") (pinfunction "1_1") (pintype "passive"))
      (node (ref "U2") (pin "3") (pinfunction "IO2_3") (pintype "bidirectional"))
      (node (ref "X1") (pin "2") (pinfunction "2_2") (pintype "bidirectional"))
    )
    (net (code "55") (name "unconnected-(IC1-PA0-Pad10)") (class "Default")
      (node (ref "IC1") (pin "10") (pinfunction "PA0_10") (pintype "bidirectional"))
    )
    (net (code "56") (name "unconnected-(IC1-PA1-Pad11)") (class "Default")
      (node (ref "IC1") (pin "11") (pinfunction "PA1_11") (pintype "bidirectional"))
    )
    (net (code "57") (name "unconnected-(IC1-PA8-Pad29)") (class "Default")
      (node (ref "IC1") (pin "29") (pinfunction "PA8_29") (pintype "bidirectional"))
    )
    (net (code "58") (name "unconnected-(IC1-PC13-Pad2)") (class "Default")
      (node (ref "IC1") (pin "2") (pinfunction "PC13_2") (pintype "bidirectional"))
    )
    (net (code "59") (name "unconnected-(IC1-PC14_OSC32IN-Pad3)") (class "Default")
      (node (ref "IC1") (pin "3") (pinfunction "PC14_OSC32IN_3") (pintype "bidirectional"))
    )
    (net (code "60") (name "unconnected-(IC1-PC15_OSC32OUT-Pad4)") (class "Default")
      (node (ref "IC1") (pin "4") (pinfunction "PC15_OSC32OUT_4") (pintype "bidirectional"))
    )
    (net (code "61") (name "unconnected-(TC1-Pad7)") (class "Default")
      (node (ref "TC1") (pin "7") (pinfunction "7_7") (pintype "passive"))
    )
  )
)
